# interface-switches.net
KiCad netlist of a schematic drawn in Altium Designer
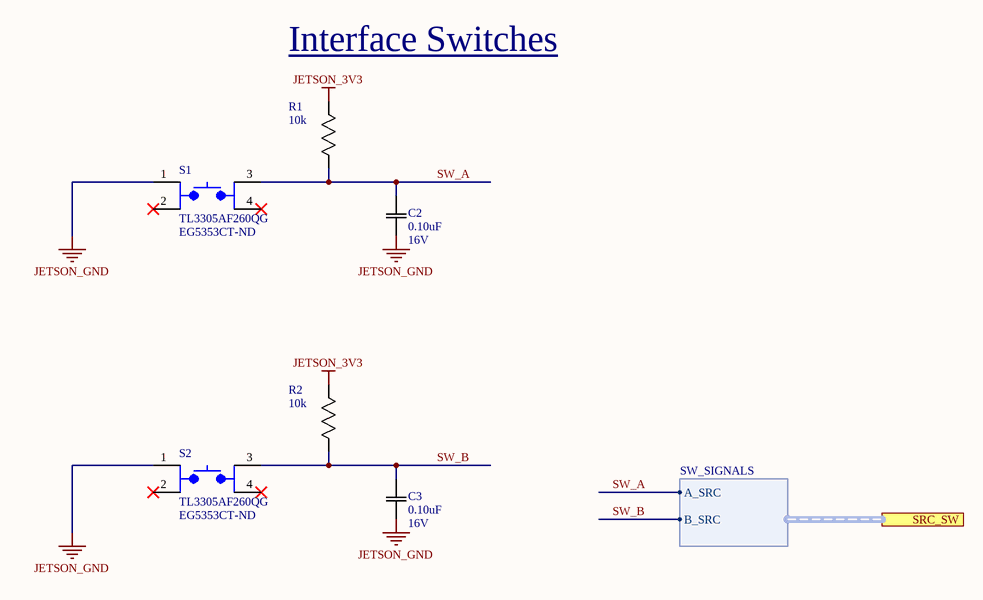
[diagram p0: interface-switches.SchDoc]

(export (version "E")
  (design (tool "Eeschema 10.0.6"))
  (components
    (comp (ref "C2")
      (value "0.10uF")
      (footprint "0603")
      (description "CAP CER 0.10UF 16V X5R 0603")
      (fields
        (field (name "TOLERANCE") "10%")
        (field (name "RATING") "16V")
        (field (name "PART NUMBER") "CAP 0.10uF 16V")
      )
      (libsource (lib "capacitor_library") (part "CAP 0.10uF 16V"))
    )
    (comp (ref "C3")
      (value "0.10uF")
      (footprint "0603")
      (description "CAP CER 0.10UF 16V X5R 0603")
      (fields
        (field (name "TOLERANCE") "10%")
        (field (name "RATING") "16V")
        (field (name "PART NUMBER") "CAP 0.10uF 16V")
      )
      (libsource (lib "capacitor_library") (part "CAP 0.10uF 16V"))
    )
    (comp (ref "R1")
      (value "10k")
      (footprint "0603")
      (description "RES SMD 10K OHM 5% 1/8W 0805")
      (fields (field (name "TOLERANCE") "5%") (field (name "PART NUMBER") "RES 10k 1/8W - 5%"))
      (libsource (lib "Resistor_Library") (part "RES 10k 1/8W 5%"))
    )
    (comp (ref "R2")
      (value "10k")
      (footprint "0603")
      (description "RES SMD 10K OHM 5% 1/8W 0805")
      (fields (field (name "TOLERANCE") "5%") (field (name "PART NUMBER") "RES 10k 1/8W - 5%"))
      (libsource (lib "Resistor_Library") (part "RES 10k 1/8W 5%"))
    )
    (comp (ref "S1")
      (value "TL3305AF260QG")
      (footprint "SW_TL3305AF260QG")
      (description "Tactile Switch SPST-NO Top Actuated Surface Mount")
      (fields
        (field (name "MF") "E-Switch")
        (field (name "SUPPLIER PART NUMBER 1") "EG5353CT-ND")
        (field (name "PART NUMBER") "SW PUSH SMD")
      )
      (libsource (lib "Switch_Library") (part "SW PUSH SMD"))
    )
    (comp (ref "S2")
      (value "TL3305AF260QG")
      (footprint "SW_TL3305AF260QG")
      (description "Tactile Switch SPST-NO Top Actuated Surface Mount")
      (fields
        (field (name "MF") "E-Switch")
        (field (name "SUPPLIER PART NUMBER 1") "EG5353CT-ND")
        (field (name "PART NUMBER") "SW PUSH SMD")
      )
      (libsource (lib "Switch_Library") (part "SW PUSH SMD"))
    )
  )
  (nets
    (net (code "2") (name "/SW_A") (class "Default")
      (node (ref "C2") (pin "2") (pinfunction "C2_2") (pintype "passive"))
      (node (ref "R1") (pin "2") (pinfunction "R2_2") (pintype "passive"))
      (node (ref "S1") (pin "3") (pinfunction "3_3") (pintype "passive"))
    )
    (net (code "3") (name "/SW_B") (class "Default")
      (node (ref "C3") (pin "2") (pinfunction "C2_2") (pintype "passive"))
      (node (ref "R2") (pin "2") (pinfunction "R2_2") (pintype "passive"))
      (node (ref "S2") (pin "3") (pinfunction "3_3") (pintype "passive"))
    )
    (net (code "5") (name "JETSON_3V3") (class "Default")
      (node (ref "R1") (pin "1") (pinfunction "R1_1") (pintype "passive"))
      (node (ref "R2") (pin "1") (pinfunction "R1_1") (pintype "passive"))
    )
    (net (code "6") (name "JETSON_GND") (class "Default")
      (node (ref "C2") (pin "1") (pinfunction "C1_1") (pintype "passive"))
      (node (ref "C3") (pin "1") (pinfunction "C1_1") (pintype "passive"))
      (node (ref "S1") (pin "1") (pinfunction "1_1") (pintype "passive"))
      (node (ref "S2") (pin "1") (pinfunction "1_1") (pintype "passive"))
    )
    (net (code "7") (name "unconnected-(S1-Pad2)") (class "Default")
      (node (ref "S1") (pin "2") (pinfunction "2_2") (pintype "passive+no_connect"))
    )
    (net (code "8") (name "unconnected-(S1-Pad4)") (class "Default")
      (node (ref "S1") (pin "4") (pinfunction "4_4") (pintype "passive+no_connect"))
    )
    (net (code "9") (name "unconnected-(S2-Pad2)") (class "Default")
      (node (ref "S2") (pin "2") (pinfunction "2_2") (pintype "passive+no_connect"))
    )
    (net (code "10") (name "unconnected-(S2-Pad4)") (class "Default")
      (node (ref "S2") (pin "4") (pinfunction "4_4") (pintype "passive+no_connect"))
    )
  )
)
